# schematic.net
KiCad netlist of a schematic drawn in EAGLE
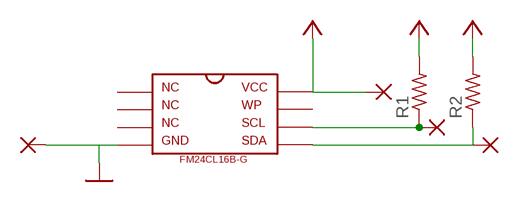
[diagram p0: schematic, sheet 1]

(export (version "E")
  (design (tool "Eeschema 10.0.6"))
  (components
    (comp (ref "GND")
      (value "SMD2")
      (footprint "eagle-import:SMD1,27-2,54")
      (libsource (lib "eagle-import") (part "SMD2"))
    )
    (comp (ref "R1")
      (value "R-US_M0805")
      (footprint "eagle-import:M0805")
      (libsource (lib "eagle-import") (part "R-US_M0805"))
    )
    (comp (ref "R2")
      (value "R-US_M0805")
      (footprint "eagle-import:M0805")
      (libsource (lib "eagle-import") (part "R-US_M0805"))
    )
    (comp (ref "SCL")
      (value "SMD2")
      (footprint "eagle-import:SMD1,27-2,54")
      (libsource (lib "eagle-import") (part "SMD2"))
    )
    (comp (ref "SDA")
      (value "SMD2")
      (footprint "eagle-import:SMD1,27-2,54")
      (libsource (lib "eagle-import") (part "SMD2"))
    )
    (comp (ref "U$1")
      (value "FM24CL16B-G")
      (footprint "eagle-import:FM24CL16B-G")
      (libsource (lib "eagle-import") (part "FM24CL16B-G"))
    )
    (comp (ref "VCC")
      (value "SMD2")
      (footprint "eagle-import:SMD1,27-2,54")
      (libsource (lib "eagle-import") (part "SMD2"))
    )
  )
  (nets
    (net (code "1") (name "+3V3") (class "Default")
      (node (ref "R1") (pin "2") (pinfunction "2_2") (pintype "passive"))
      (node (ref "R2") (pin "2") (pinfunction "2_2") (pintype "passive"))
      (node (ref "U$1") (pin "8") (pinfunction "8_8") (pintype "power_in"))
      (node (ref "VCC") (pin "1") (pinfunction "P_1") (pintype "passive"))
    )
    (net (code "2") (name "GND") (class "Default")
      (node (ref "GND") (pin "1") (pinfunction "P_1") (pintype "passive"))
      (node (ref "U$1") (pin "4") (pinfunction "4_4") (pintype "power_in"))
    )
    (net (code "3") (name "Net-(SCL-P)") (class "Default")
      (node (ref "R1") (pin "1") (pinfunction "1_1") (pintype "passive"))
      (node (ref "SCL") (pin "1") (pinfunction "P_1") (pintype "passive"))
      (node (ref "U$1") (pin "6") (pinfunction "6_6") (pintype "input"))
    )
    (net (code "4") (name "Net-(SDA-P)") (class "Default")
      (node (ref "R2") (pin "1") (pinfunction "1_1") (pintype "passive"))
      (node (ref "SDA") (pin "1") (pinfunction "P_1") (pintype "passive"))
      (node (ref "U$1") (pin "5") (pinfunction "5_5") (pintype "input"))
    )
    (net (code "5") (name "unconnected-(U$1-Pad1)") (class "Default")
      (node (ref "U$1") (pin "1") (pinfunction "1_1") (pintype "no_connect"))
    )
    (net (code "6") (name "unconnected-(U$1-Pad2)") (class "Default")
      (node (ref "U$1") (pin "2") (pinfunction "2_2") (pintype "no_connect"))
    )
    (net (code "7") (name "unconnected-(U$1-Pad3)") (class "Default")
      (node (ref "U$1") (pin "3") (pinfunction "3_3") (pintype "no_connect"))
    )
    (net (code "8") (name "unconnected-(U$1-Pad7)") (class "Default")
      (node (ref "U$1") (pin "7") (pinfunction "7_7") (pintype "bidirectional"))
    )
  )
)
